# Sheet_1.net
KiCad netlist of a schematic drawn in EasyEDA
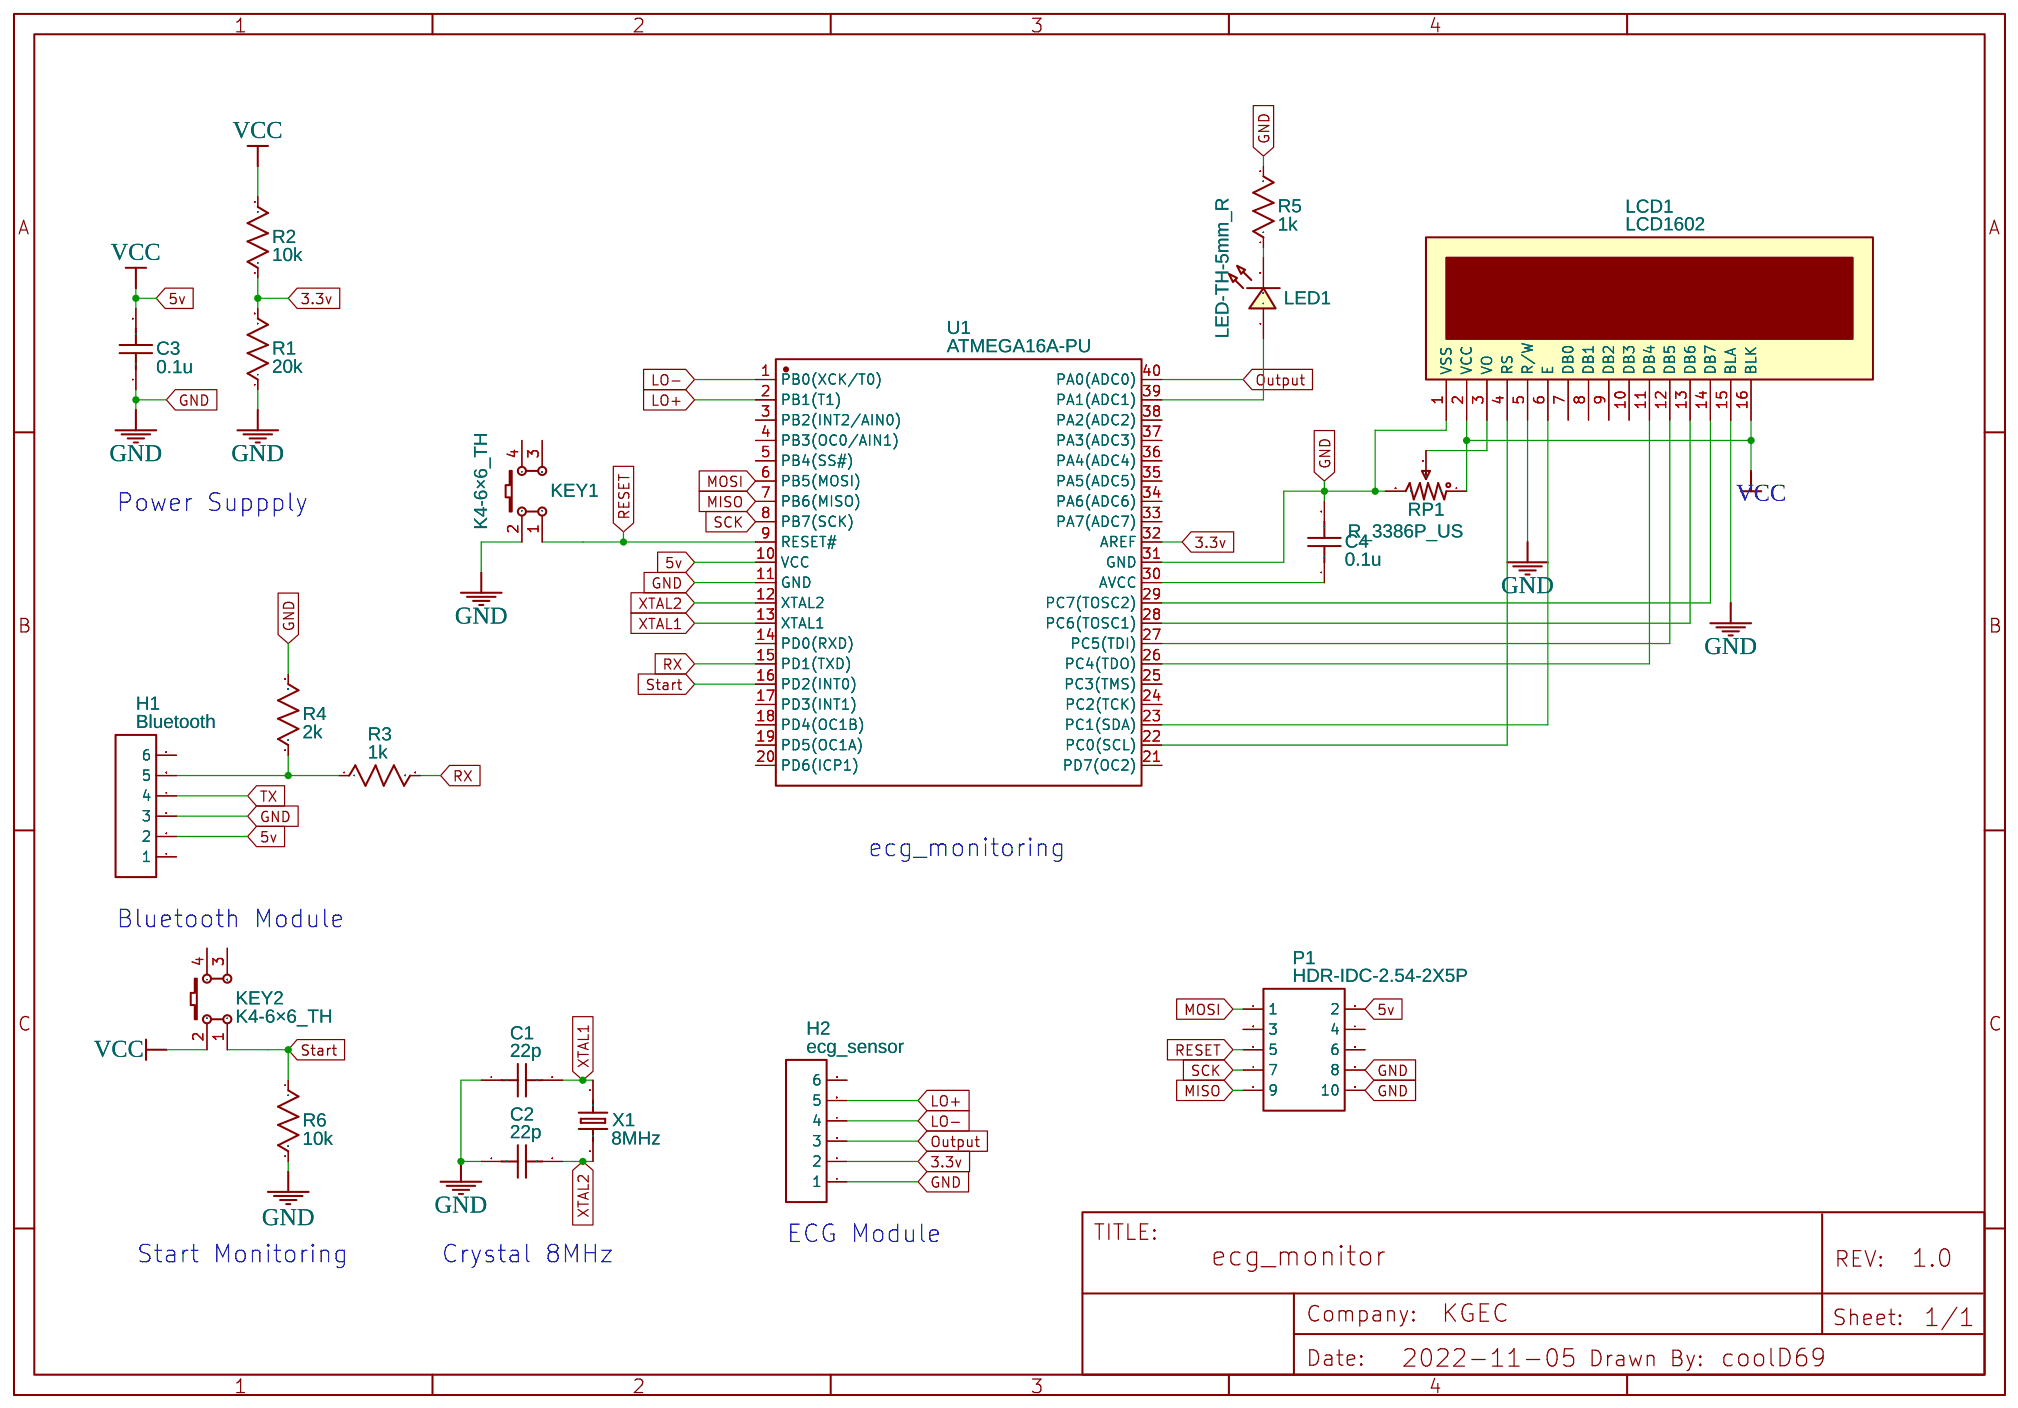
[diagram p0: schematic sheet]

(export (version "E")
  (design (tool "Eeschema 10.0.6"))
  (components
    (comp (ref "C1") (value "22p") (libsource (lib "") (part "C_RAD-0.1_US_1")))
    (comp (ref "C2") (value "22p") (libsource (lib "") (part "C_RAD-0.1_US_1")))
    (comp (ref "C3") (value "0.1u") (libsource (lib "") (part "C_RAD-0.1_US")))
    (comp (ref "C4") (value "0.1u") (libsource (lib "") (part "C_RAD-0.1_US")))
    (comp (ref "H1")
      (value "Bluetooth")
      (fields (field (name "BOM_Supplier Part") "C40877"))
      (libsource (lib "") (part "HDR-F-2.54_1x6"))
    )
    (comp (ref "H2")
      (value "ecg_sensor")
      (fields (field (name "BOM_Supplier Part") "C40877"))
      (libsource (lib "") (part "HDR-F-2.54_1x6"))
    )
    (comp (ref "KEY1")
      (value "K4-6×6_TH")
      (fields
        (field (name "BOM_Manufacturer Part") "K2-1102DP-E4SW-04")
        (field (name "BOM_Supplier Part") "C136684")
      )
      (libsource (lib "") (part "K4-6×6_TH"))
    )
    (comp (ref "KEY2")
      (value "K4-6×6_TH")
      (fields
        (field (name "BOM_Manufacturer Part") "K2-1102DP-E4SW-04")
        (field (name "BOM_Supplier Part") "C136684")
      )
      (libsource (lib "") (part "K4-6×6_TH"))
    )
    (comp (ref "LCD1")
      (value "LCD1602")
      (fields
        (field (name "BOM_Manufacturer Part") "LCM1602K-NSW-BBW")
        (field (name "BOM_Supplier Part") "C83275")
      )
      (libsource (lib "") (part "LCD1602"))
    )
    (comp (ref "LED1")
      (value "LED-TH-5mm_R")
      (fields
        (field (name "BOM_Manufacturer Part") "333-2SURD/S530-A3")
        (field (name "BOM_Supplier Part") "C87271")
      )
      (libsource (lib "") (part "LED-TH-5mm_R"))
    )
    (comp (ref "P1")
      (value "HDR-IDC-2.54-2X5P")
      (fields
        (field (name "BOM_Manufacturer Part") "IDC Box 2.54mm 2X5P")
        (field (name "BOM_Supplier Part") "C5665")
      )
      (libsource (lib "") (part "HDR-IDC-2.54-2X5P"))
    )
    (comp (ref "R1") (value "20k") (libsource (lib "") (part "R_AXIAL-0.5_US_2")))
    (comp (ref "R2") (value "10k") (libsource (lib "") (part "R_AXIAL-0.5_US_2")))
    (comp (ref "R3") (value "1k") (libsource (lib "") (part "R_AXIAL-0.5_US")))
    (comp (ref "R4") (value "2k") (libsource (lib "") (part "R_AXIAL-0.5_US_2")))
    (comp (ref "R5") (value "1k") (libsource (lib "") (part "R_AXIAL-0.5_US_2")))
    (comp (ref "R6") (value "10k") (libsource (lib "") (part "R_AXIAL-0.5_US_1")))
    (comp (ref "RP1") (value "R_3386P_US") (libsource (lib "") (part "R_3386P_US")))
    (comp (ref "U1")
      (value "ATMEGA16A-PU")
      (fields (field (name "BOM_Supplier Part") "C30504"))
      (libsource (lib "") (part "ATMEGA16A-PU"))
    )
    (comp (ref "X1")
      (value "8MHz")
      (fields
        (field (name "BOM_Manufacturer Part") "TAXD12M2GLFBET2T")
        (field (name "BOM_Supplier Part") "C127674")
      )
      (libsource (lib "") (part "HC-49S12MHZ20PF30PPM"))
    )
  )
  (nets
    (net (code "1") (name "3.3v") (class "Default")
      (node (ref "H2") (pin "2") (pinfunction "2_2") (pintype "input"))
      (node (ref "R1") (pin "2") (pinfunction "2_2") (pintype "unspecified"))
      (node (ref "R2") (pin "1") (pinfunction "1_1") (pintype "unspecified"))
      (node (ref "U1") (pin "32") (pinfunction "AREF_32") (pintype "unspecified"))
    )
    (net (code "2") (name "5v") (class "Default")
      (node (ref "C3") (pin "2") (pinfunction "2_2") (pintype "unspecified"))
      (node (ref "H1") (pin "2") (pinfunction "2_2") (pintype "input"))
      (node (ref "KEY2") (pin "2") (pinfunction "2_2") (pintype "unspecified"))
      (node (ref "LCD1") (pin "16") (pinfunction "BLK_16") (pintype "unspecified"))
      (node (ref "LCD1") (pin "2") (pinfunction "VCC_2") (pintype "unspecified"))
      (node (ref "P1") (pin "2") (pinfunction "2_2") (pintype "unspecified"))
      (node (ref "R2") (pin "2") (pinfunction "2_2") (pintype "unspecified"))
      (node (ref "RP1") (pin "1") (pinfunction "1_1") (pintype "unspecified"))
      (node (ref "U1") (pin "10") (pinfunction "VCC_10") (pintype "unspecified"))
    )
    (net (code "3") (name "GND") (class "Default")
      (node (ref "C1") (pin "1") (pinfunction "1_1") (pintype "unspecified"))
      (node (ref "C2") (pin "1") (pinfunction "1_1") (pintype "unspecified"))
      (node (ref "C3") (pin "1") (pinfunction "1_1") (pintype "unspecified"))
      (node (ref "C4") (pin "2") (pinfunction "2_2") (pintype "unspecified"))
      (node (ref "H1") (pin "3") (pinfunction "3_3") (pintype "input"))
      (node (ref "H2") (pin "1") (pinfunction "1_1") (pintype "input"))
      (node (ref "KEY1") (pin "2") (pinfunction "2_2") (pintype "unspecified"))
      (node (ref "LCD1") (pin "1") (pinfunction "VSS_1") (pintype "unspecified"))
      (node (ref "LCD1") (pin "15") (pinfunction "BLA_15") (pintype "unspecified"))
      (node (ref "LCD1") (pin "5") (pinfunction "R/W_5") (pintype "unspecified"))
      (node (ref "P1") (pin "10") (pinfunction "10_10") (pintype "unspecified"))
      (node (ref "P1") (pin "8") (pinfunction "8_8") (pintype "unspecified"))
      (node (ref "R1") (pin "1") (pinfunction "1_1") (pintype "unspecified"))
      (node (ref "R4") (pin "2") (pinfunction "2_2") (pintype "unspecified"))
      (node (ref "R5") (pin "2") (pinfunction "2_2") (pintype "unspecified"))
      (node (ref "R6") (pin "2") (pinfunction "2_2") (pintype "unspecified"))
      (node (ref "RP1") (pin "3") (pinfunction "3_3") (pintype "unspecified"))
      (node (ref "U1") (pin "11") (pinfunction "GND_11") (pintype "unspecified"))
      (node (ref "U1") (pin "31") (pinfunction "GND_31") (pintype "unspecified"))
    )
    (net (code "4") (name "LO+") (class "Default")
      (node (ref "H2") (pin "5") (pinfunction "5_5") (pintype "input"))
      (node (ref "U1") (pin "2") (pinfunction "PB1(T1)_2") (pintype "unspecified"))
    )
    (net (code "5") (name "LO-") (class "Default")
      (node (ref "H2") (pin "4") (pinfunction "4_4") (pintype "input"))
      (node (ref "U1") (pin "1") (pinfunction "PB0(XCK/T0)_1") (pintype "unspecified"))
    )
    (net (code "6") (name "MISO") (class "Default")
      (node (ref "P1") (pin "9") (pinfunction "9_9") (pintype "unspecified"))
      (node (ref "U1") (pin "7") (pinfunction "PB6(MISO)_7") (pintype "unspecified"))
    )
    (net (code "7") (name "MOSI") (class "Default")
      (node (ref "P1") (pin "1") (pinfunction "1_1") (pintype "unspecified"))
      (node (ref "U1") (pin "6") (pinfunction "PB5(MOSI)_6") (pintype "unspecified"))
    )
    (net (code "8") (name "Net-(H1-Pad5)") (class "Default")
      (node (ref "H1") (pin "5") (pinfunction "5_5") (pintype "input"))
      (node (ref "R3") (pin "1") (pinfunction "1_1") (pintype "unspecified"))
      (node (ref "R4") (pin "1") (pinfunction "1_1") (pintype "unspecified"))
    )
    (net (code "9") (name "Net-(LCD1-DB4)") (class "Default")
      (node (ref "LCD1") (pin "11") (pinfunction "DB4_11") (pintype "unspecified"))
      (node (ref "U1") (pin "26") (pinfunction "PC4(TDO)_26") (pintype "unspecified"))
    )
    (net (code "10") (name "Net-(LCD1-DB5)") (class "Default")
      (node (ref "LCD1") (pin "12") (pinfunction "DB5_12") (pintype "unspecified"))
      (node (ref "U1") (pin "27") (pinfunction "PC5(TDI)_27") (pintype "unspecified"))
    )
    (net (code "11") (name "Net-(LCD1-DB6)") (class "Default")
      (node (ref "LCD1") (pin "13") (pinfunction "DB6_13") (pintype "unspecified"))
      (node (ref "U1") (pin "28") (pinfunction "PC6(TOSC1)_28") (pintype "unspecified"))
    )
    (net (code "12") (name "Net-(LCD1-DB7)") (class "Default")
      (node (ref "LCD1") (pin "14") (pinfunction "DB7_14") (pintype "unspecified"))
      (node (ref "U1") (pin "29") (pinfunction "PC7(TOSC2)_29") (pintype "unspecified"))
    )
    (net (code "13") (name "Net-(LCD1-E)") (class "Default")
      (node (ref "LCD1") (pin "6") (pinfunction "E_6") (pintype "unspecified"))
      (node (ref "U1") (pin "23") (pinfunction "PC1(SDA)_23") (pintype "unspecified"))
    )
    (net (code "14") (name "Net-(LCD1-RS)") (class "Default")
      (node (ref "LCD1") (pin "4") (pinfunction "RS_4") (pintype "unspecified"))
      (node (ref "U1") (pin "22") (pinfunction "PC0(SCL)_22") (pintype "unspecified"))
    )
    (net (code "15") (name "Net-(LCD1-VO)") (class "Default")
      (node (ref "LCD1") (pin "3") (pinfunction "VO_3") (pintype "unspecified"))
      (node (ref "RP1") (pin "2") (pinfunction "2_2") (pintype "unspecified"))
    )
    (net (code "16") (name "Net-(LED1-Pad2)") (class "Default")
      (node (ref "LED1") (pin "2") (pinfunction "2_2") (pintype "unspecified"))
      (node (ref "R5") (pin "1") (pinfunction "1_1") (pintype "unspecified"))
    )
    (net (code "17") (name "Net-(U1-AVCC)") (class "Default")
      (node (ref "C4") (pin "1") (pinfunction "1_1") (pintype "unspecified"))
      (node (ref "U1") (pin "30") (pinfunction "AVCC_30") (pintype "unspecified"))
    )
    (net (code "18") (name "Net-(U1-PA1(ADC1))") (class "Default")
      (node (ref "LED1") (pin "1") (pinfunction "1_1") (pintype "unspecified"))
      (node (ref "U1") (pin "39") (pinfunction "PA1(ADC1)_39") (pintype "unspecified"))
    )
    (net (code "19") (name "Output") (class "Default")
      (node (ref "H2") (pin "3") (pinfunction "3_3") (pintype "input"))
      (node (ref "U1") (pin "40") (pinfunction "PA0(ADC0)_40") (pintype "unspecified"))
    )
    (net (code "20") (name "RESET") (class "Default")
      (node (ref "KEY1") (pin "1") (pinfunction "1_1") (pintype "unspecified"))
      (node (ref "P1") (pin "5") (pinfunction "5_5") (pintype "unspecified"))
      (node (ref "U1") (pin "9") (pinfunction "RESET#_9") (pintype "unspecified"))
    )
    (net (code "21") (name "RX") (class "Default")
      (node (ref "R3") (pin "2") (pinfunction "2_2") (pintype "unspecified"))
      (node (ref "U1") (pin "15") (pinfunction "PD1(TXD)_15") (pintype "unspecified"))
    )
    (net (code "22") (name "SCK") (class "Default")
      (node (ref "P1") (pin "7") (pinfunction "7_7") (pintype "unspecified"))
      (node (ref "U1") (pin "8") (pinfunction "PB7(SCK)_8") (pintype "unspecified"))
    )
    (net (code "23") (name "Start") (class "Default")
      (node (ref "KEY2") (pin "1") (pinfunction "1_1") (pintype "unspecified"))
      (node (ref "R6") (pin "1") (pinfunction "1_1") (pintype "unspecified"))
      (node (ref "U1") (pin "16") (pinfunction "PD2(INT0)_16") (pintype "unspecified"))
    )
    (net (code "24") (name "TX") (class "Default")
      (node (ref "H1") (pin "4") (pinfunction "4_4") (pintype "input"))
    )
    (net (code "25") (name "XTAL1") (class "Default")
      (node (ref "C1") (pin "2") (pinfunction "2_2") (pintype "unspecified"))
      (node (ref "U1") (pin "13") (pinfunction "XTAL1_13") (pintype "unspecified"))
      (node (ref "X1") (pin "2") (pinfunction "2_2") (pintype "unspecified"))
    )
    (net (code "26") (name "XTAL2") (class "Default")
      (node (ref "C2") (pin "2") (pinfunction "2_2") (pintype "unspecified"))
      (node (ref "U1") (pin "12") (pinfunction "XTAL2_12") (pintype "unspecified"))
      (node (ref "X1") (pin "1") (pinfunction "1_1") (pintype "unspecified"))
    )
    (net (code "27") (name "unconnected-(H1-Pad1)") (class "Default")
      (node (ref "H1") (pin "1") (pinfunction "1_1") (pintype "input"))
    )
    (net (code "28") (name "unconnected-(H1-Pad6)") (class "Default")
      (node (ref "H1") (pin "6") (pinfunction "6_6") (pintype "input"))
    )
    (net (code "29") (name "unconnected-(H2-Pad6)") (class "Default")
      (node (ref "H2") (pin "6") (pinfunction "6_6") (pintype "input"))
    )
    (net (code "30") (name "unconnected-(KEY1-Pad3)") (class "Default")
      (node (ref "KEY1") (pin "3") (pinfunction "3_3") (pintype "unspecified"))
    )
    (net (code "31") (name "unconnected-(KEY1-Pad4)") (class "Default")
      (node (ref "KEY1") (pin "4") (pinfunction "4_4") (pintype "unspecified"))
    )
    (net (code "32") (name "unconnected-(KEY2-Pad3)") (class "Default")
      (node (ref "KEY2") (pin "3") (pinfunction "3_3") (pintype "unspecified"))
    )
    (net (code "33") (name "unconnected-(KEY2-Pad4)") (class "Default")
      (node (ref "KEY2") (pin "4") (pinfunction "4_4") (pintype "unspecified"))
    )
    (net (code "34") (name "unconnected-(LCD1-DB0-Pad7)") (class "Default")
      (node (ref "LCD1") (pin "7") (pinfunction "DB0_7") (pintype "unspecified"))
    )
    (net (code "35") (name "unconnected-(LCD1-DB1-Pad8)") (class "Default")
      (node (ref "LCD1") (pin "8") (pinfunction "DB1_8") (pintype "unspecified"))
    )
    (net (code "36") (name "unconnected-(LCD1-DB2-Pad9)") (class "Default")
      (node (ref "LCD1") (pin "9") (pinfunction "DB2_9") (pintype "unspecified"))
    )
    (net (code "37") (name "unconnected-(LCD1-DB3-Pad10)") (class "Default")
      (node (ref "LCD1") (pin "10") (pinfunction "DB3_10") (pintype "unspecified"))
    )
    (net (code "38") (name "unconnected-(P1-Pad3)") (class "Default")
      (node (ref "P1") (pin "3") (pinfunction "3_3") (pintype "unspecified"))
    )
    (net (code "39") (name "unconnected-(P1-Pad4)") (class "Default")
      (node (ref "P1") (pin "4") (pinfunction "4_4") (pintype "unspecified"))
    )
    (net (code "40") (name "unconnected-(P1-Pad6)") (class "Default")
      (node (ref "P1") (pin "6") (pinfunction "6_6") (pintype "unspecified"))
    )
    (net (code "41") (name "unconnected-(U1-PA2(ADC2)-Pad38)") (class "Default")
      (node (ref "U1") (pin "38") (pinfunction "PA2(ADC2)_38") (pintype "unspecified"))
    )
    (net (code "42") (name "unconnected-(U1-PA3(ADC3)-Pad37)") (class "Default")
      (node (ref "U1") (pin "37") (pinfunction "PA3(ADC3)_37") (pintype "unspecified"))
    )
    (net (code "43") (name "unconnected-(U1-PA4(ADC4)-Pad36)") (class "Default")
      (node (ref "U1") (pin "36") (pinfunction "PA4(ADC4)_36") (pintype "unspecified"))
    )
    (net (code "44") (name "unconnected-(U1-PA5(ADC5)-Pad35)") (class "Default")
      (node (ref "U1") (pin "35") (pinfunction "PA5(ADC5)_35") (pintype "unspecified"))
    )
    (net (code "45") (name "unconnected-(U1-PA6(ADC6)-Pad34)") (class "Default")
      (node (ref "U1") (pin "34") (pinfunction "PA6(ADC6)_34") (pintype "unspecified"))
    )
    (net (code "46") (name "unconnected-(U1-PA7(ADC7)-Pad33)") (class "Default")
      (node (ref "U1") (pin "33") (pinfunction "PA7(ADC7)_33") (pintype "unspecified"))
    )
    (net (code "47") (name "unconnected-(U1-PB2(INT2{slash}AIN0)-Pad3)") (class "Default")
      (node (ref "U1") (pin "3") (pinfunction "PB2(INT2/AIN0)_3") (pintype "unspecified"))
    )
    (net (code "48") (name "unconnected-(U1-PB3(OC0{slash}AIN1)-Pad4)") (class "Default")
      (node (ref "U1") (pin "4") (pinfunction "PB3(OC0/AIN1)_4") (pintype "unspecified"))
    )
    (net (code "49") (name "unconnected-(U1-PB4(SS#)-Pad5)") (class "Default")
      (node (ref "U1") (pin "5") (pinfunction "PB4(SS#)_5") (pintype "unspecified"))
    )
    (net (code "50") (name "unconnected-(U1-PC2(TCK)-Pad24)") (class "Default")
      (node (ref "U1") (pin "24") (pinfunction "PC2(TCK)_24") (pintype "unspecified"))
    )
    (net (code "51") (name "unconnected-(U1-PC3(TMS)-Pad25)") (class "Default")
      (node (ref "U1") (pin "25") (pinfunction "PC3(TMS)_25") (pintype "unspecified"))
    )
    (net (code "52") (name "unconnected-(U1-PD0(RXD)-Pad14)") (class "Default")
      (node (ref "U1") (pin "14") (pinfunction "PD0(RXD)_14") (pintype "unspecified"))
    )
    (net (code "53") (name "unconnected-(U1-PD3(INT1)-Pad17)") (class "Default")
      (node (ref "U1") (pin "17") (pinfunction "PD3(INT1)_17") (pintype "unspecified"))
    )
    (net (code "54") (name "unconnected-(U1-PD4(OC1B)-Pad18)") (class "Default")
      (node (ref "U1") (pin "18") (pinfunction "PD4(OC1B)_18") (pintype "unspecified"))
    )
    (net (code "55") (name "unconnected-(U1-PD5(OC1A)-Pad19)") (class "Default")
      (node (ref "U1") (pin "19") (pinfunction "PD5(OC1A)_19") (pintype "unspecified"))
    )
    (net (code "56") (name "unconnected-(U1-PD6(ICP1)-Pad20)") (class "Default")
      (node (ref "U1") (pin "20") (pinfunction "PD6(ICP1)_20") (pintype "unspecified"))
    )
    (net (code "57") (name "unconnected-(U1-PD7(OC2)-Pad21)") (class "Default")
      (node (ref "U1") (pin "21") (pinfunction "PD7(OC2)_21") (pintype "unspecified"))
    )
  )
)
